# SCH_Obsolicard_2025-10-24.net
KiCad netlist of a schematic drawn in EasyEDA
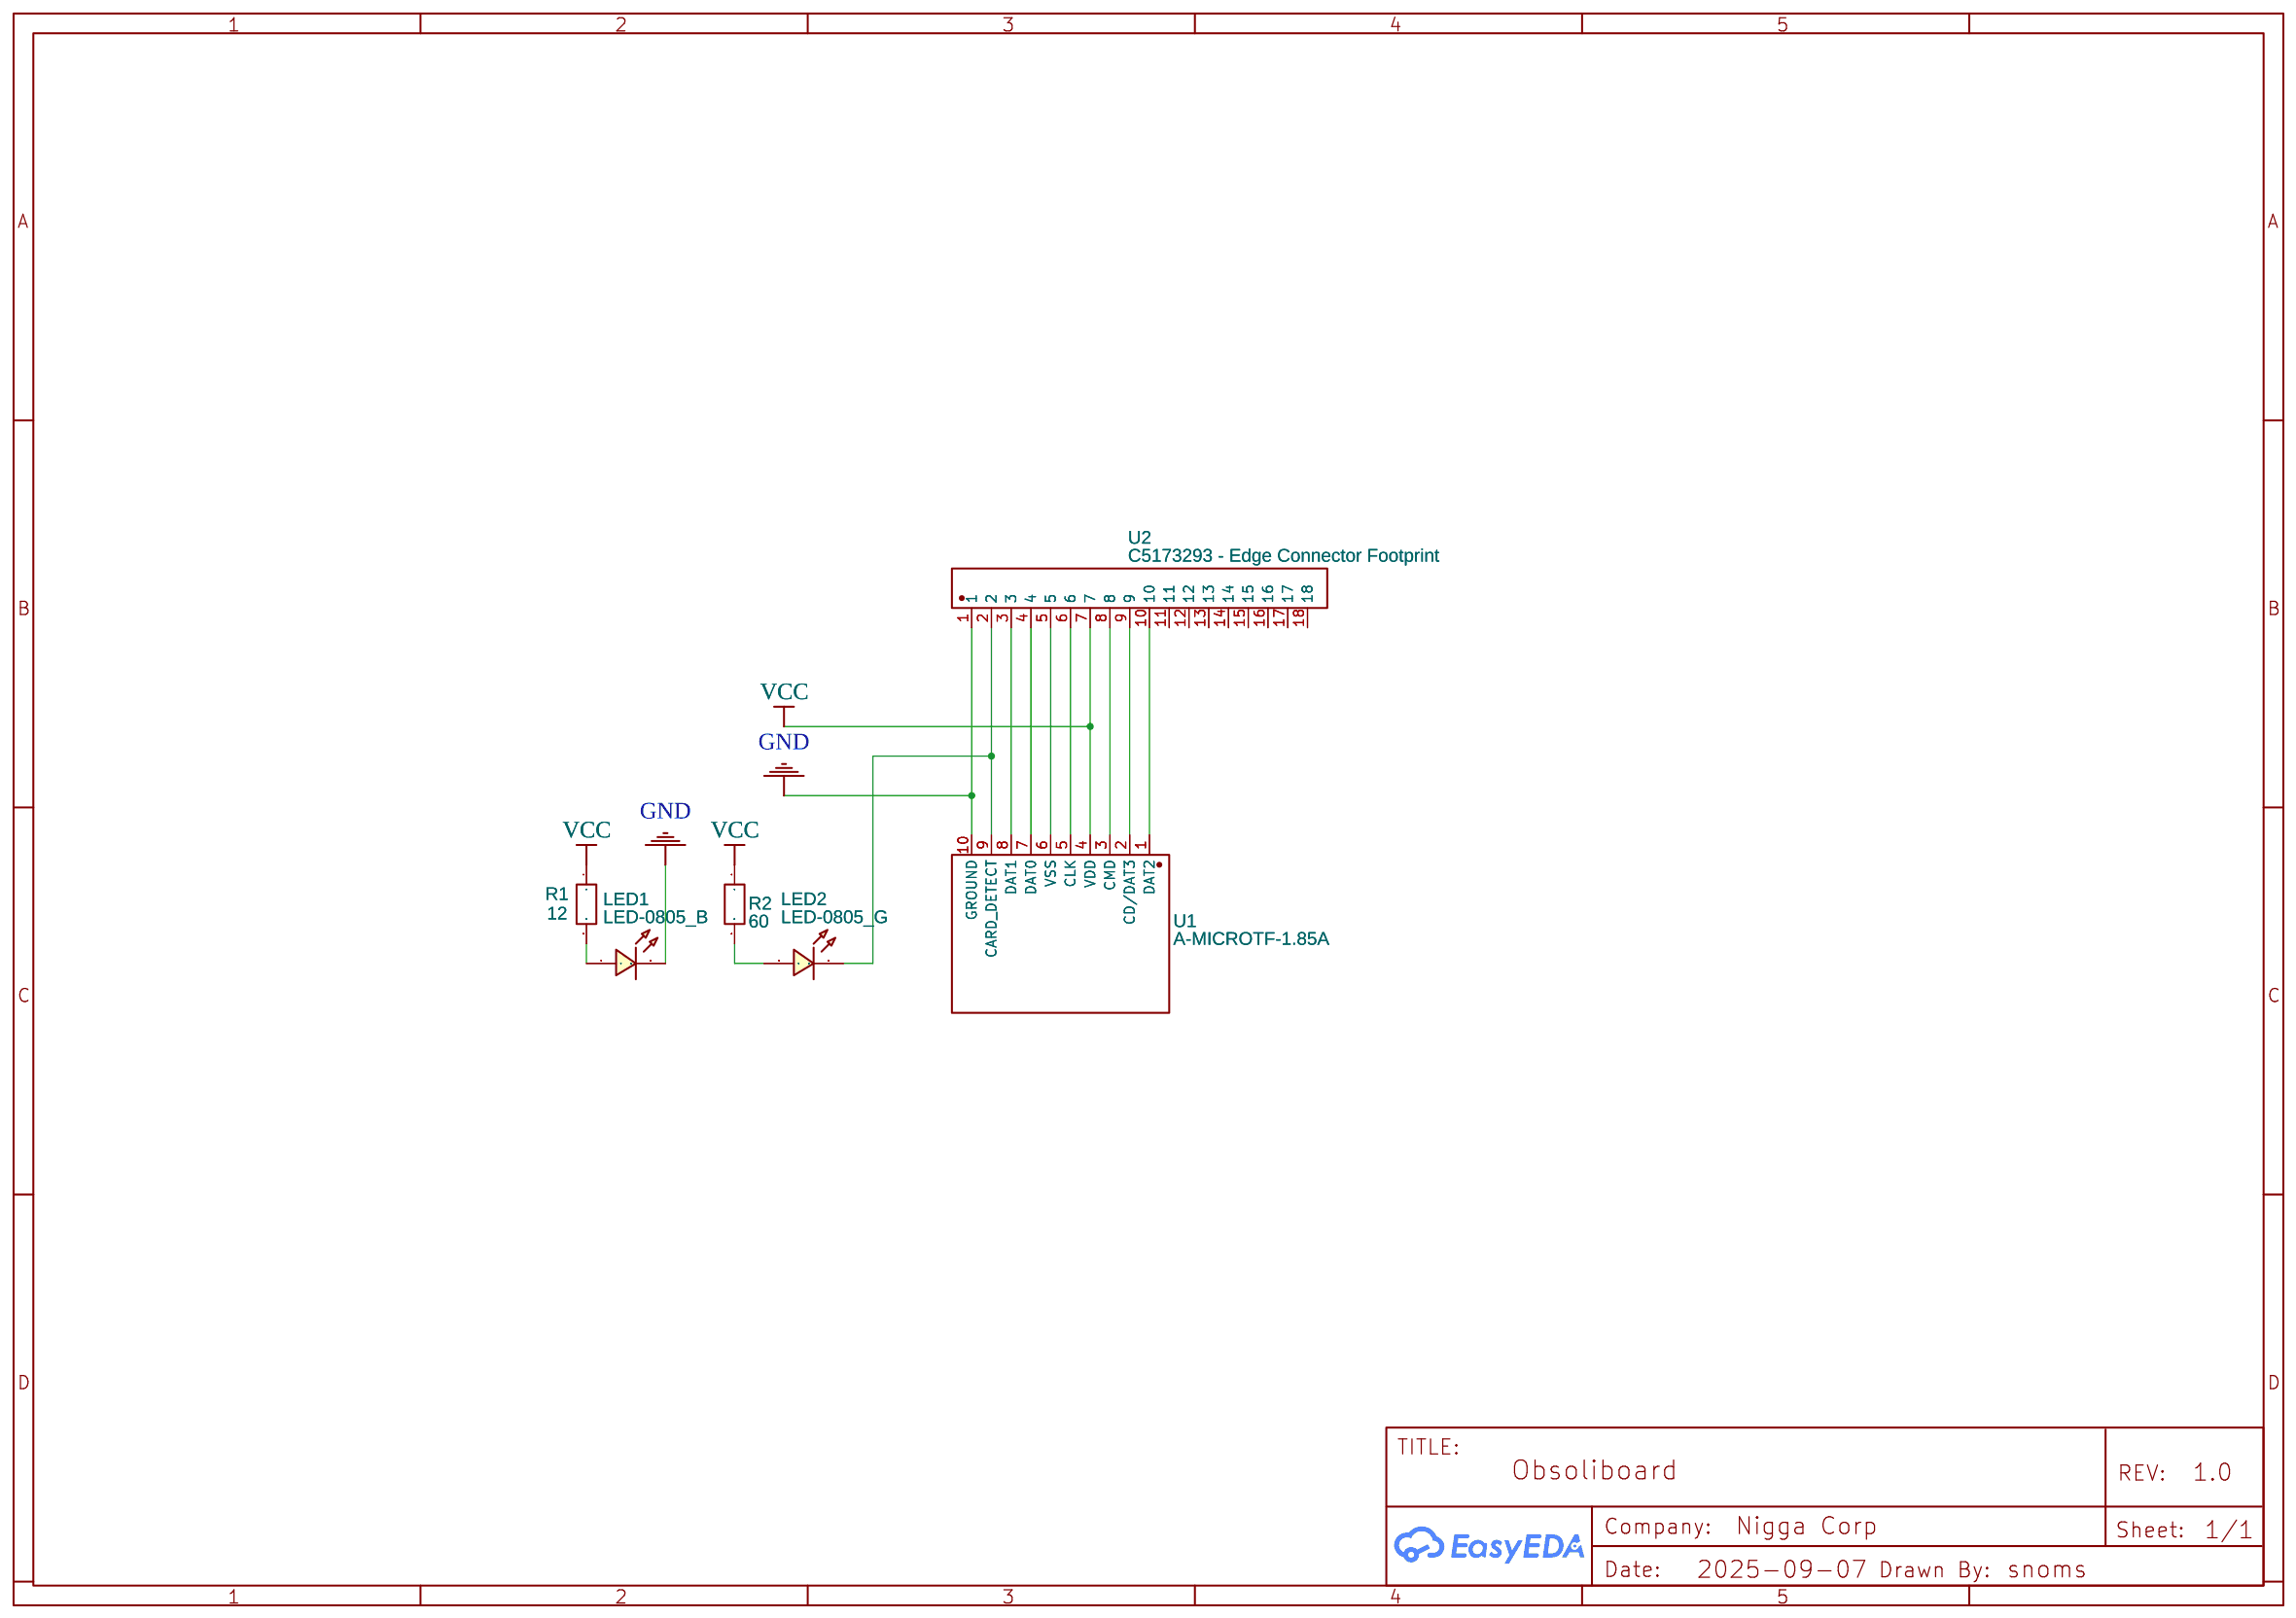
[diagram p0: schematic sheet]

(export (version "E")
  (design (tool "Eeschema 10.0.6"))
  (components
    (comp (ref "LED1")
      (value "LED-0805_B")
      (fields (field (name "Manufacturer Part") "YLED0805B") (field (name "Manufacturer") "YONGYUTAI"))
      (libsource (lib "") (part "LED-0805_B"))
    )
    (comp (ref "LED2")
      (value "LED-0805_G")
      (fields (field (name "Manufacturer Part") "KT-0805G") (field (name "Manufacturer") "Hubei KENTO Elec"))
      (libsource (lib "") (part "LED-0805_G"))
    )
    (comp (ref "R1") (value "12") (libsource (lib "") (part "R_0805_EU")))
    (comp (ref "R2") (value "60") (libsource (lib "") (part "R_0805_EU")))
    (comp (ref "U1")
      (value "A-MICROTF-1.85A")
      (fields
        (field (name "Manufacturer Part") "A-MicroTF-1.85A")
        (field (name "Manufacturer") "MyAntenna(摩天射频)")
      )
      (libsource (lib "") (part "A-MICROTF-1.85A"))
    )
    (comp (ref "U2")
      (value "C5173293 - Edge Connector Footprint")
      (fields (field (name "Manufacturer") "WingTat"))
      (libsource (lib "") (part "C5173293 - Edge Connector Footprint"))
    )
  )
  (nets
    (net (code "1") (name "GND") (class "Default")
      (node (ref "LED1") (pin "2") (pinfunction "2_2") (pintype "unspecified"))
      (node (ref "U1") (pin "10") (pinfunction "GROUND_10") (pintype "unspecified"))
      (node (ref "U2") (pin "1") (pinfunction "1_1") (pintype "unspecified"))
    )
    (net (code "2") (name "Net-(LED1-Pad1)") (class "Default")
      (node (ref "LED1") (pin "1") (pinfunction "1_1") (pintype "unspecified"))
      (node (ref "R1") (pin "2") (pinfunction "2_2") (pintype "unspecified"))
    )
    (net (code "3") (name "Net-(LED2-Pad1)") (class "Default")
      (node (ref "LED2") (pin "1") (pinfunction "1_1") (pintype "unspecified"))
      (node (ref "R2") (pin "2") (pinfunction "2_2") (pintype "unspecified"))
    )
    (net (code "4") (name "Net-(U1-CARD_DETECT)") (class "Default")
      (node (ref "LED2") (pin "2") (pinfunction "2_2") (pintype "unspecified"))
      (node (ref "U1") (pin "9") (pinfunction "CARD_DETECT_9") (pintype "unspecified"))
      (node (ref "U2") (pin "2") (pinfunction "2_2") (pintype "unspecified"))
    )
    (net (code "5") (name "Net-(U1-CD{slash}DAT3)") (class "Default")
      (node (ref "U1") (pin "2") (pinfunction "CD/DAT3_2") (pintype "unspecified"))
      (node (ref "U2") (pin "9") (pinfunction "9_9") (pintype "unspecified"))
    )
    (net (code "6") (name "Net-(U1-CLK)") (class "Default")
      (node (ref "U1") (pin "5") (pinfunction "CLK_5") (pintype "unspecified"))
      (node (ref "U2") (pin "6") (pinfunction "6_6") (pintype "unspecified"))
    )
    (net (code "7") (name "Net-(U1-CMD)") (class "Default")
      (node (ref "U1") (pin "3") (pinfunction "CMD_3") (pintype "unspecified"))
      (node (ref "U2") (pin "8") (pinfunction "8_8") (pintype "unspecified"))
    )
    (net (code "8") (name "Net-(U1-DAT0)") (class "Default")
      (node (ref "U1") (pin "7") (pinfunction "DAT0_7") (pintype "unspecified"))
      (node (ref "U2") (pin "4") (pinfunction "4_4") (pintype "unspecified"))
    )
    (net (code "9") (name "Net-(U1-DAT1)") (class "Default")
      (node (ref "U1") (pin "8") (pinfunction "DAT1_8") (pintype "unspecified"))
      (node (ref "U2") (pin "3") (pinfunction "3_3") (pintype "unspecified"))
    )
    (net (code "10") (name "Net-(U1-DAT2)") (class "Default")
      (node (ref "U1") (pin "1") (pinfunction "DAT2_1") (pintype "unspecified"))
      (node (ref "U2") (pin "10") (pinfunction "10_10") (pintype "unspecified"))
    )
    (net (code "11") (name "Net-(U1-VSS)") (class "Default")
      (node (ref "U1") (pin "6") (pinfunction "VSS_6") (pintype "unspecified"))
      (node (ref "U2") (pin "5") (pinfunction "5_5") (pintype "unspecified"))
    )
    (net (code "12") (name "VCC") (class "Default")
      (node (ref "R1") (pin "1") (pinfunction "1_1") (pintype "unspecified"))
      (node (ref "R2") (pin "1") (pinfunction "1_1") (pintype "unspecified"))
      (node (ref "U1") (pin "4") (pinfunction "VDD_4") (pintype "unspecified"))
      (node (ref "U2") (pin "7") (pinfunction "7_7") (pintype "unspecified"))
    )
    (net (code "13") (name "unconnected-(U2-Pad11)") (class "Default")
      (node (ref "U2") (pin "11") (pinfunction "11_11") (pintype "unspecified"))
    )
    (net (code "14") (name "unconnected-(U2-Pad12)") (class "Default")
      (node (ref "U2") (pin "12") (pinfunction "12_12") (pintype "unspecified"))
    )
    (net (code "15") (name "unconnected-(U2-Pad13)") (class "Default")
      (node (ref "U2") (pin "13") (pinfunction "13_13") (pintype "unspecified"))
    )
    (net (code "16") (name "unconnected-(U2-Pad14)") (class "Default")
      (node (ref "U2") (pin "14") (pinfunction "14_14") (pintype "unspecified"))
    )
    (net (code "17") (name "unconnected-(U2-Pad15)") (class "Default")
      (node (ref "U2") (pin "15") (pinfunction "15_15") (pintype "unspecified"))
    )
    (net (code "18") (name "unconnected-(U2-Pad16)") (class "Default")
      (node (ref "U2") (pin "16") (pinfunction "16_16") (pintype "unspecified"))
    )
    (net (code "19") (name "unconnected-(U2-Pad17)") (class "Default")
      (node (ref "U2") (pin "17") (pinfunction "17_17") (pintype "unspecified"))
    )
    (net (code "20") (name "unconnected-(U2-Pad18)") (class "Default")
      (node (ref "U2") (pin "18") (pinfunction "18_18") (pintype "unspecified"))
    )
  )
)
